# MainPage.net
KiCad netlist of a schematic drawn in Altium Designer
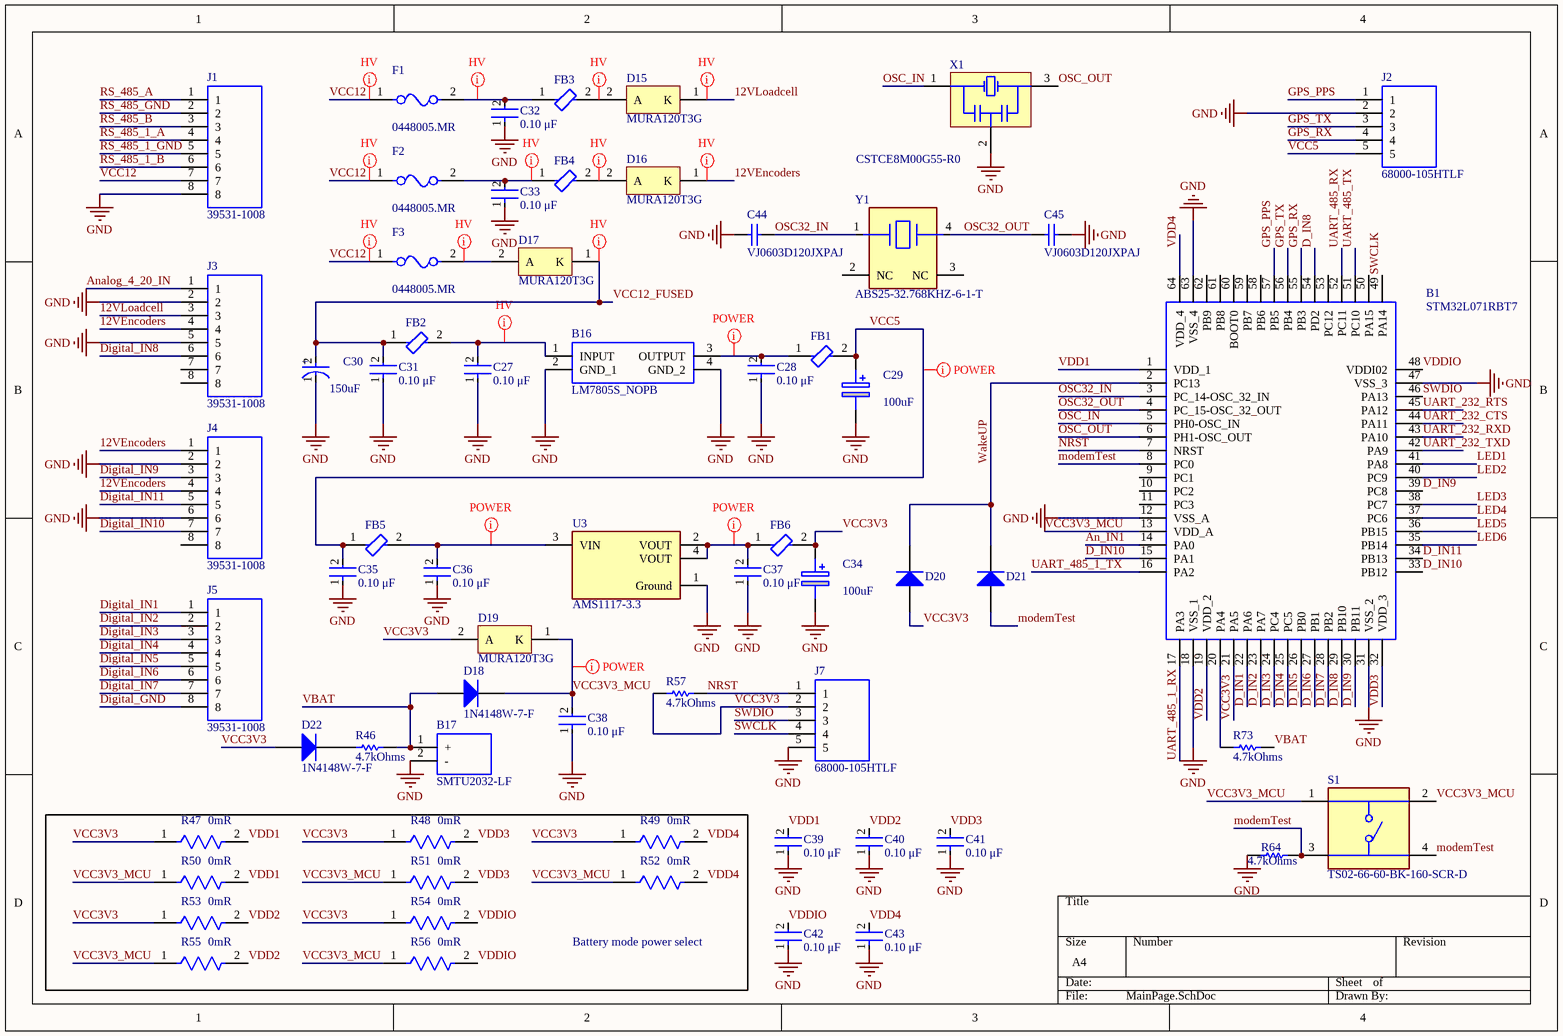
[diagram p0: MainPage.SchDoc]

(export (version "E")
  (design (tool "Eeschema 10.0.6"))
  (components
    (comp (ref "B1")
      (value "STM32L071RBT7")
      (footprint "QFP50P1200X1200X160-64N")
      (description "ARM Microcontrollers - MCU 16/32-BITS MICROS")
      (fields (field (name "MOUSER PART NUMBER") "511-STM32L071RBT7"))
      (libsource (lib "Schlib2") (part "STM32L071RBT7"))
    )
    (comp (ref "B16")
      (value "LM7805S_NOPB")
      (footprint "KTT0003B")
      (description "1.5-A, Wide VIN Fixed Voltage Regulators")
      (fields
        (field (name "MOUSER PART NUMBER") "595-LM7805S/NOPB")
        (field (name "MANUFACTURER_PART_NUMBER") "LM7805S/NOPB")
      )
      (libsource (lib "Schlib2") (part "LM7805S_NOPB"))
    )
    (comp (ref "B17")
      (value "SMTU2032-LF")
      (footprint "SMTU2032LF")
      (description "Coin Cell Battery Holders SFC MNT FOR CR2032")
      (fields (field (name "MOUSER PART NUMBER") "614-SMTU2032-LF"))
      (libsource (lib "Schlib2") (part "SMTU2032-LF"))
    )
    (comp (ref "C27")
      (value "0.10 μF")
      (footprint "FP-C0805C-DN-MFG")
      (description "C0805 0.10 μF X7R 30ppm/°C 10.00% 50 V")
      (fields
        (field (name "MANUFACTURER") "KEMET")
        (field (name "MANUFACTURER PART NUMBER") "C0805C104K5RAC7411")
      )
      (libsource (lib "Altium Content Vault") (part "b4654b650e69147ec39a6b967a45e02"))
    )
    (comp (ref "C28")
      (value "0.10 μF")
      (footprint "FP-C0805C-DN-MFG")
      (description "C0805 0.10 μF X7R 30ppm/°C 10.00% 50 V")
      (fields
        (field (name "MANUFACTURER") "KEMET")
        (field (name "MANUFACTURER PART NUMBER") "C0805C104K5RAC7411")
      )
      (libsource (lib "Altium Content Vault") (part "b4654b650e69147ec39a6b967a45e02"))
    )
    (comp (ref "C29")
      (value "T520B107M006ATE040")
      (footprint "T520B")
      (fields (field (name "MOUSER PART NUMBER") "80-T520B107M6ATE40") (field (name "CAPACITANCE") "100uF"))
      (libsource (lib "Schlib2") (part "T520B107M006ATE040"))
    )
    (comp (ref "C30")
      (value "TAJE157K020RNJ")
      (footprint "FP-TAJE-MFG")
      (description "150uF 20V  ±10% 300mΩ 2917  SMD Tantalum Capacitor")
      (fields (field (name "CAPACITANCE") "150uF") (field (name "TOLERANCE") "10%"))
      (libsource (lib "Altium Content Vault") (part "203bc49f2ac43e59fd269a8c329ed05"))
    )
    (comp (ref "C31")
      (value "0.10 μF")
      (footprint "FP-C0805C-DN-MFG")
      (description "C0805 0.10 μF X7R 30ppm/°C 10.00% 50 V")
      (fields
        (field (name "MANUFACTURER") "KEMET")
        (field (name "MANUFACTURER PART NUMBER") "C0805C104K5RAC7411")
      )
      (libsource (lib "Altium Content Vault") (part "b4654b650e69147ec39a6b967a45e02"))
    )
    (comp (ref "C32")
      (value "0.10 μF")
      (footprint "FP-C0805C-DN-MFG")
      (description "C0805 0.10 μF X7R 30ppm/°C 10.00% 50 V")
      (fields
        (field (name "MANUFACTURER") "KEMET")
        (field (name "MANUFACTURER PART NUMBER") "C0805C104K5RAC7411")
      )
      (libsource (lib "Altium Content Vault") (part "b4654b650e69147ec39a6b967a45e02"))
    )
    (comp (ref "C33")
      (value "0.10 μF")
      (footprint "FP-C0805C-DN-MFG")
      (description "C0805 0.10 μF X7R 30ppm/°C 10.00% 50 V")
      (fields
        (field (name "MANUFACTURER") "KEMET")
        (field (name "MANUFACTURER PART NUMBER") "C0805C104K5RAC7411")
      )
      (libsource (lib "Altium Content Vault") (part "b4654b650e69147ec39a6b967a45e02"))
    )
    (comp (ref "C34")
      (value "T520B107M006ATE040")
      (footprint "T520B")
      (fields (field (name "MOUSER PART NUMBER") "80-T520B107M6ATE40") (field (name "CAPACITANCE") "100uF"))
      (libsource (lib "Schlib2") (part "T520B107M006ATE040"))
    )
    (comp (ref "C35")
      (value "0.10 μF")
      (footprint "FP-C0805C-DN-MFG")
      (description "C0805 0.10 μF X7R 30ppm/°C 10.00% 50 V")
      (fields
        (field (name "MANUFACTURER") "KEMET")
        (field (name "MANUFACTURER PART NUMBER") "C0805C104K5RAC7411")
      )
      (libsource (lib "Altium Content Vault") (part "b4654b650e69147ec39a6b967a45e02"))
    )
    (comp (ref "C36")
      (value "0.10 μF")
      (footprint "FP-C0805C-DN-MFG")
      (description "C0805 0.10 μF X7R 30ppm/°C 10.00% 50 V")
      (fields
        (field (name "MANUFACTURER") "KEMET")
        (field (name "MANUFACTURER PART NUMBER") "C0805C104K5RAC7411")
      )
      (libsource (lib "Altium Content Vault") (part "b4654b650e69147ec39a6b967a45e02"))
    )
    (comp (ref "C37")
      (value "0.10 μF")
      (footprint "FP-C0805C-DN-MFG")
      (description "C0805 0.10 μF X7R 30ppm/°C 10.00% 50 V")
      (fields
        (field (name "MANUFACTURER") "KEMET")
        (field (name "MANUFACTURER PART NUMBER") "C0805C104K5RAC7411")
      )
      (libsource (lib "Altium Content Vault") (part "b4654b650e69147ec39a6b967a45e02"))
    )
    (comp (ref "C38")
      (value "0.10 μF")
      (footprint "FP-C0805C-DN-MFG")
      (description "C0805 0.10 μF X7R 30ppm/°C 10.00% 50 V")
      (fields
        (field (name "MANUFACTURER") "KEMET")
        (field (name "MANUFACTURER PART NUMBER") "C0805C104K5RAC7411")
      )
      (libsource (lib "Altium Content Vault") (part "b4654b650e69147ec39a6b967a45e02"))
    )
    (comp (ref "C39")
      (value "0.10 μF")
      (footprint "FP-C0805C-DN-MFG")
      (description "C0805 0.10 μF X7R 30ppm/°C 10.00% 50 V")
      (fields
        (field (name "MANUFACTURER") "KEMET")
        (field (name "MANUFACTURER PART NUMBER") "C0805C104K5RAC7411")
      )
      (libsource (lib "Altium Content Vault") (part "b4654b650e69147ec39a6b967a45e02"))
    )
    (comp (ref "C40")
      (value "0.10 μF")
      (footprint "FP-C0805C-DN-MFG")
      (description "C0805 0.10 μF X7R 30ppm/°C 10.00% 50 V")
      (fields
        (field (name "MANUFACTURER") "KEMET")
        (field (name "MANUFACTURER PART NUMBER") "C0805C104K5RAC7411")
      )
      (libsource (lib "Altium Content Vault") (part "b4654b650e69147ec39a6b967a45e02"))
    )
    (comp (ref "C41")
      (value "0.10 μF")
      (footprint "FP-C0805C-DN-MFG")
      (description "C0805 0.10 μF X7R 30ppm/°C 10.00% 50 V")
      (fields
        (field (name "MANUFACTURER") "KEMET")
        (field (name "MANUFACTURER PART NUMBER") "C0805C104K5RAC7411")
      )
      (libsource (lib "Altium Content Vault") (part "b4654b650e69147ec39a6b967a45e02"))
    )
    (comp (ref "C42")
      (value "0.10 μF")
      (footprint "FP-C0805C-DN-MFG")
      (description "C0805 0.10 μF X7R 30ppm/°C 10.00% 50 V")
      (fields
        (field (name "MANUFACTURER") "KEMET")
        (field (name "MANUFACTURER PART NUMBER") "C0805C104K5RAC7411")
      )
      (libsource (lib "Altium Content Vault") (part "b4654b650e69147ec39a6b967a45e02"))
    )
    (comp (ref "C43")
      (value "0.10 μF")
      (footprint "FP-C0805C-DN-MFG")
      (description "C0805 0.10 μF X7R 30ppm/°C 10.00% 50 V")
      (fields
        (field (name "MANUFACTURER") "KEMET")
        (field (name "MANUFACTURER PART NUMBER") "C0805C104K5RAC7411")
      )
      (libsource (lib "Altium Content Vault") (part "b4654b650e69147ec39a6b967a45e02"))
    )
    (comp (ref "C44")
      (value "VJ0603D120JXPAJ")
      (footprint "CAPC1608X92X38LL15T08")
      (fields (field (name "MANUFACTURER") "Vitramon"))
      (libsource (lib "Altium Content Vault") (part "CAP"))
    )
    (comp (ref "C45")
      (value "VJ0603D120JXPAJ")
      (footprint "CAPC1608X92X38LL15T08")
      (fields (field (name "MANUFACTURER") "Vitramon"))
      (libsource (lib "Altium Content Vault") (part "CAP"))
    )
    (comp (ref "D15")
      (value "MURA120T3G")
      (footprint "ONSC-SMA-2-403D-02_V")
      (description "Surface Mount Ultrafast Power Rectifier, 2-Pin SMA, Pb-Free, Tape and Reel")
      (fields (field (name "MANUFACTURER") "On Semiconductor"))
      (libsource (lib "Altium Content Vault") (part "ONSC-D-K1A2-2_A"))
    )
    (comp (ref "D16")
      (value "MURA120T3G")
      (footprint "ONSC-SMA-2-403D-02_V")
      (description "Surface Mount Ultrafast Power Rectifier, 2-Pin SMA, Pb-Free, Tape and Reel")
      (fields (field (name "MANUFACTURER") "On Semiconductor"))
      (libsource (lib "Altium Content Vault") (part "ONSC-D-K1A2-2_A"))
    )
    (comp (ref "D17")
      (value "MURA120T3G")
      (footprint "ONSC-SMA-2-403D-02_V")
      (description "Surface Mount Ultrafast Power Rectifier, 2-Pin SMA, Pb-Free, Tape and Reel")
      (fields (field (name "MANUFACTURER") "On Semiconductor"))
      (libsource (lib "Altium Content Vault") (part "ONSC-D-K1A2-2_A"))
    )
    (comp (ref "D18")
      (value "1N4148W-7-F")
      (footprint "DIOD-SOD123-2_V")
      (description "Fast Switching Diode, 100 V, 0.15 A, -65 to 150 degC, 2-Pin?SOD123, RoHS, Tape and Reel")
      (fields (field (name "MANUFACTURER") "DiodesIncorporated"))
      (libsource (lib "Altium Content Vault") (part "D-AK-2"))
    )
    (comp (ref "D19")
      (value "MURA120T3G")
      (footprint "ONSC-SMA-2-403D-02_V")
      (description "Surface Mount Ultrafast Power Rectifier, 2-Pin SMA, Pb-Free, Tape and Reel")
      (fields (field (name "MANUFACTURER") "On Semiconductor"))
      (libsource (lib "Altium Content Vault") (part "ONSC-D-K1A2-2_A"))
    )
    (comp (ref "D20")
      (value "1N4148W-7-F")
      (footprint "DIOD-SOD123-2_V")
      (description "Fast Switching Diode, 100 V, 0.15 A, -65 to 150 degC, 2-Pin?SOD123, RoHS, Tape and Reel")
      (fields (field (name "MANUFACTURER") "DiodesIncorporated"))
      (libsource (lib "Altium Content Vault") (part "D-AK-2"))
    )
    (comp (ref "D21")
      (value "1N4148W-7-F")
      (footprint "DIOD-SOD123-2_V")
      (description "Fast Switching Diode, 100 V, 0.15 A, -65 to 150 degC, 2-Pin?SOD123, RoHS, Tape and Reel")
      (fields (field (name "MANUFACTURER") "DiodesIncorporated"))
      (libsource (lib "Altium Content Vault") (part "D-AK-2"))
    )
    (comp (ref "D22")
      (value "1N4148W-7-F")
      (footprint "DIOD-SOD123-2_V")
      (description "Fast Switching Diode, 100 V, 0.15 A, -65 to 150 degC, 2-Pin?SOD123, RoHS, Tape and Reel")
      (fields (field (name "MANUFACTURER") "DiodesIncorporated"))
      (libsource (lib "Altium Content Vault") (part "D-AK-2"))
    )
    (comp (ref "F1")
      (value "0448005.MR")
      (footprint "FP-0448-MFG")
      (description "FUSE BRD MNT 5A 125VAC/VDC 2SMD")
      (fields
        (field (name "OCTOPART") "https://octopart.com/0448005.mr-littelfuse-672815")
        (field (name "MANUFACTURER") "Littelfuse")
      )
      (libsource (lib "Altium Content Vault") (part "5bcf9b9f640e542cf0359d10258e979"))
    )
    (comp (ref "F2")
      (value "0448005.MR")
      (footprint "FP-0448-MFG")
      (description "FUSE BRD MNT 5A 125VAC/VDC 2SMD")
      (fields
        (field (name "OCTOPART") "https://octopart.com/0448005.mr-littelfuse-672815")
        (field (name "MANUFACTURER") "Littelfuse")
      )
      (libsource (lib "Altium Content Vault") (part "5bcf9b9f640e542cf0359d10258e979"))
    )
    (comp (ref "F3")
      (value "0448005.MR")
      (footprint "FP-0448-MFG")
      (description "FUSE BRD MNT 5A 125VAC/VDC 2SMD")
      (fields
        (field (name "OCTOPART") "https://octopart.com/0448005.mr-littelfuse-672815")
        (field (name "MANUFACTURER") "Littelfuse")
      )
      (libsource (lib "Altium Content Vault") (part "5bcf9b9f640e542cf0359d10258e979"))
    )
    (comp (ref "FB1")
      (value "BLM41PG181SH1L")
      (footprint "FP-BLM41-0_2-a1_2-MFG")
      (description "Ferrite Bead, 1806, 180Ω @ 100MHz, 25%, 0.02Ω, 3.5A")
      (fields (field (name "TOLERANCE") "25%"))
      (libsource (lib "Altium Content Vault") (part "5f30dd21d616792df468990f7003faa"))
    )
    (comp (ref "FB2")
      (value "BLM41PG181SH1L")
      (footprint "FP-BLM41-0_2-a1_2-MFG")
      (description "Ferrite Bead, 1806, 180Ω @ 100MHz, 25%, 0.02Ω, 3.5A")
      (fields (field (name "TOLERANCE") "25%"))
      (libsource (lib "Altium Content Vault") (part "5f30dd21d616792df468990f7003faa"))
    )
    (comp (ref "FB3")
      (value "BLM41PG181SH1L")
      (footprint "FP-BLM41-0_2-a1_2-MFG")
      (description "Ferrite Bead, 1806, 180Ω @ 100MHz, 25%, 0.02Ω, 3.5A")
      (fields (field (name "TOLERANCE") "25%"))
      (libsource (lib "Altium Content Vault") (part "5f30dd21d616792df468990f7003faa"))
    )
    (comp (ref "FB4")
      (value "BLM41PG181SH1L")
      (footprint "FP-BLM41-0_2-a1_2-MFG")
      (description "Ferrite Bead, 1806, 180Ω @ 100MHz, 25%, 0.02Ω, 3.5A")
      (fields (field (name "TOLERANCE") "25%"))
      (libsource (lib "Altium Content Vault") (part "5f30dd21d616792df468990f7003faa"))
    )
    (comp (ref "FB5")
      (value "BLM41PG181SH1L")
      (footprint "FP-BLM41-0_2-a1_2-MFG")
      (description "Ferrite Bead, 1806, 180Ω @ 100MHz, 25%, 0.02Ω, 3.5A")
      (fields (field (name "TOLERANCE") "25%"))
      (libsource (lib "Altium Content Vault") (part "5f30dd21d616792df468990f7003faa"))
    )
    (comp (ref "FB6")
      (value "BLM41PG181SH1L")
      (footprint "FP-BLM41-0_2-a1_2-MFG")
      (description "Ferrite Bead, 1806, 180Ω @ 100MHz, 25%, 0.02Ω, 3.5A")
      (fields (field (name "TOLERANCE") "25%"))
      (libsource (lib "Altium Content Vault") (part "5f30dd21d616792df468990f7003faa"))
    )
    (comp (ref "J1")
      (value "39531-1008")
      (footprint "RHDR8W140P0X508_1X8_4264X830X1240P")
      (description "Pluggable Terminal Blocks 5.08MM EURO HEADER VERT BLK 8CKT")
      (fields (field (name "MOUSER PART NUMBER") "538-39531-1008"))
      (libsource (lib "Schlib2") (part "39531-1008"))
    )
    (comp (ref "J2")
      (value "68000-105HTLF")
      (footprint "HDRV5W67P0X254_1X5_1270X241X858P")
      (description "68000-105HTLF-B/S SR HDR 1*5")
      (fields (field (name "MOUSER PART NUMBER") "649-68000-105HTLF"))
      (libsource (lib "Schlib2") (part "68000-105HTLF"))
    )
    (comp (ref "J3")
      (value "39531-1008")
      (footprint "RHDR8W140P0X508_1X8_4264X830X1240P")
      (description "Pluggable Terminal Blocks 5.08MM EURO HEADER VERT BLK 8CKT")
      (fields (field (name "MOUSER PART NUMBER") "538-39531-1008"))
      (libsource (lib "Schlib2") (part "39531-1008"))
    )
    (comp (ref "J4")
      (value "39531-1008")
      (footprint "RHDR8W140P0X508_1X8_4264X830X1240P")
      (description "Pluggable Terminal Blocks 5.08MM EURO HEADER VERT BLK 8CKT")
      (fields (field (name "MOUSER PART NUMBER") "538-39531-1008"))
      (libsource (lib "Schlib2") (part "39531-1008"))
    )
    (comp (ref "J5")
      (value "39531-1008")
      (footprint "RHDR8W140P0X508_1X8_4264X830X1240P")
      (description "Pluggable Terminal Blocks 5.08MM EURO HEADER VERT BLK 8CKT")
      (fields (field (name "MOUSER PART NUMBER") "538-39531-1008"))
      (libsource (lib "Schlib2") (part "39531-1008"))
    )
    (comp (ref "J7")
      (value "68000-105HTLF")
      (footprint "HDRV5W67P0X254_1X5_1270X241X858P")
      (description "68000-105HTLF-B/S SR HDR 1*5")
      (fields (field (name "MOUSER PART NUMBER") "649-68000-105HTLF"))
      (libsource (lib "Schlib2") (part "68000-105HTLF"))
    )
    (comp (ref "R46")
      (value "RC0603FR-074K7L")
      (footprint "RESC1608X55X25LL10T15")
      (description "Chip Resistor, 4.7 KOhm, +/- 1%, 0.1 W, -55 to 155 degC, 0603 (1608 Metric), RoHS, Tape and Reel")
      (fields
        (field (name "MANUFACTURER") "Yageo")
        (field (name "RESISTANCE") "4.7kOhms")
        (field (name "TOLERANCE") "1%")
      )
      (libsource (lib "Altium Content Vault") (part "RES-2"))
    )
    (comp (ref "R47")
      (value "CRCW06030000Z0EAHP")
      (footprint "FP-CRCW0603-HPe3-MFG")
      (description "RES Thick Film, 0Ω, , 0.33W, , 0603")
      (fields (field (name "RESISTANCE") "0mR"))
      (libsource (lib "Altium Content Vault") (part "1029c3af85768c4190bb7ad29bc67b5"))
    )
    (comp (ref "R48")
      (value "CRCW06030000Z0EAHP")
      (footprint "FP-CRCW0603-HPe3-MFG")
      (description "RES Thick Film, 0Ω, , 0.33W, , 0603")
      (fields (field (name "RESISTANCE") "0mR"))
      (libsource (lib "Altium Content Vault") (part "1029c3af85768c4190bb7ad29bc67b5"))
    )
    (comp (ref "R49")
      (value "CRCW06030000Z0EAHP")
      (footprint "FP-CRCW0603-HPe3-MFG")
      (description "RES Thick Film, 0Ω, , 0.33W, , 0603")
      (fields (field (name "RESISTANCE") "0mR"))
      (libsource (lib "Altium Content Vault") (part "1029c3af85768c4190bb7ad29bc67b5"))
    )
    (comp (ref "R50")
      (value "CRCW06030000Z0EAHP")
      (footprint "FP-CRCW0603-HPe3-MFG")
      (description "RES Thick Film, 0Ω, , 0.33W, , 0603")
      (fields (field (name "RESISTANCE") "0mR"))
      (libsource (lib "Altium Content Vault") (part "1029c3af85768c4190bb7ad29bc67b5"))
    )
    (comp (ref "R51")
      (value "CRCW06030000Z0EAHP")
      (footprint "FP-CRCW0603-HPe3-MFG")
      (description "RES Thick Film, 0Ω, , 0.33W, , 0603")
      (fields (field (name "RESISTANCE") "0mR"))
      (libsource (lib "Altium Content Vault") (part "1029c3af85768c4190bb7ad29bc67b5"))
    )
    (comp (ref "R52")
      (value "CRCW06030000Z0EAHP")
      (footprint "FP-CRCW0603-HPe3-MFG")
      (description "RES Thick Film, 0Ω, , 0.33W, , 0603")
      (fields (field (name "RESISTANCE") "0mR"))
      (libsource (lib "Altium Content Vault") (part "1029c3af85768c4190bb7ad29bc67b5"))
    )
    (comp (ref "R53")
      (value "CRCW06030000Z0EAHP")
      (footprint "FP-CRCW0603-HPe3-MFG")
      (description "RES Thick Film, 0Ω, , 0.33W, , 0603")
      (fields (field (name "RESISTANCE") "0mR"))
      (libsource (lib "Altium Content Vault") (part "1029c3af85768c4190bb7ad29bc67b5"))
    )
    (comp (ref "R54")
      (value "CRCW06030000Z0EAHP")
      (footprint "FP-CRCW0603-HPe3-MFG")
      (description "RES Thick Film, 0Ω, , 0.33W, , 0603")
      (fields (field (name "RESISTANCE") "0mR"))
      (libsource (lib "Altium Content Vault") (part "1029c3af85768c4190bb7ad29bc67b5"))
    )
    (comp (ref "R55")
      (value "CRCW06030000Z0EAHP")
      (footprint "FP-CRCW0603-HPe3-MFG")
      (description "RES Thick Film, 0Ω, , 0.33W, , 0603")
      (fields (field (name "RESISTANCE") "0mR"))
      (libsource (lib "Altium Content Vault") (part "1029c3af85768c4190bb7ad29bc67b5"))
    )
    (comp (ref "R56")
      (value "CRCW06030000Z0EAHP")
      (footprint "FP-CRCW0603-HPe3-MFG")
      (description "RES Thick Film, 0Ω, , 0.33W, , 0603")
      (fields (field (name "RESISTANCE") "0mR"))
      (libsource (lib "Altium Content Vault") (part "1029c3af85768c4190bb7ad29bc67b5"))
    )
    (comp (ref "R57")
      (value "RC0603FR-074K7L")
      (footprint "RESC1608X55X25LL10T15")
      (description "Chip Resistor, 4.7 KOhm, +/- 1%, 0.1 W, -55 to 155 degC, 0603 (1608 Metric), RoHS, Tape and Reel")
      (fields
        (field (name "MANUFACTURER") "Yageo")
        (field (name "RESISTANCE") "4.7kOhms")
        (field (name "TOLERANCE") "1%")
      )
      (libsource (lib "Altium Content Vault") (part "RES-2"))
    )
    (comp (ref "R64")
      (value "RC0603FR-074K7L")
      (footprint "RESC1608X55X25LL10T15")
      (description "Chip Resistor, 4.7 KOhm, +/- 1%, 0.1 W, -55 to 155 degC, 0603 (1608 Metric), RoHS, Tape and Reel")
      (fields
        (field (name "MANUFACTURER") "Yageo")
        (field (name "RESISTANCE") "4.7kOhms")
        (field (name "TOLERANCE") "1%")
      )
      (libsource (lib "Altium Content Vault") (part "RES-2"))
    )
    (comp (ref "R73")
      (value "RC0603FR-074K7L")
      (footprint "RESC1608X55X25LL10T15")
      (description "Chip Resistor, 4.7 KOhm, +/- 1%, 0.1 W, -55 to 155 degC, 0603 (1608 Metric), RoHS, Tape and Reel")
      (fields
        (field (name "MANUFACTURER") "Yageo")
        (field (name "RESISTANCE") "4.7kOhms")
        (field (name "TOLERANCE") "1%")
      )
      (libsource (lib "Altium Content Vault") (part "RES-2"))
    )
    (comp (ref "S1")
      (value "TS02-66-60-BK-160-SCR-D")
      (footprint "SW_TS02-66-60-BK-160-SCR-D")
      (libsource (lib "Schlib2") (part "TS02-66-60-BK-160-SCR-D"))
    )
    (comp (ref "U3")
      (value "AMS1117-3.3")
      (footprint "FP-AMS1117-IPC_C")
      (description "LDO Voltage Regulators 1A, 3.3V")
      (fields
        (field (name "OCTOPART") "https://octopart.com/ams1117-3.3-advanced+monolithic+systems-25899300")
        (field (name "MANUFACTURER") "Advanced Monolithic Systems")
      )
      (libsource (lib "Altium Content Vault") (part "8bdbb5f8e77002000e30dd2845d0354"))
    )
    (comp (ref "X1")
      (value "CSTCE8M00G55-R0")
      (footprint "MURA-CSTCE_G_A-3_V")
      (description "Ceramic Resonator, 8 MHz, +/- 0.5%, -20 to 80 degC, 3-Pin SMD, RoHS, Tape and Reel")
      (fields (field (name "TOLERANCE") "0.5%") (field (name "MANUFACTURER") "Murata"))
      (libsource (lib "Altium Content Vault") (part "MURA-CSTCE_G_A-3"))
    )
    (comp (ref "Y1")
      (value "ABS25-32.768KHZ-6-1-T")
      (footprint "FP-ABS25-MFG")
      (description "CRYSTAL 32.7680KHZ 6PF SMD")
      (fields (field (name "TOLERANCE") "10ppm"))
      (libsource (lib "Altium Content Vault") (part "28be33c29b20f54059194caee89ade4"))
    )
  )
  (nets
    (net (code "1") (name "/12VEncoders") (class "Default")
      (node (ref "D16") (pin "1") (pinfunction "K_1") (pintype "passive"))
      (node (ref "J3") (pin "4") (pinfunction "4_4") (pintype "passive"))
      (node (ref "J4") (pin "1") (pinfunction "1_1") (pintype "passive"))
      (node (ref "J4") (pin "4") (pinfunction "4_4") (pintype "passive"))
    )
    (net (code "2") (name "/12VLoadcell") (class "Default")
      (node (ref "D15") (pin "1") (pinfunction "K_1") (pintype "passive"))
      (node (ref "J3") (pin "3") (pinfunction "3_3") (pintype "passive"))
    )
    (net (code "3") (name "/An_IN1") (class "Default")
      (node (ref "B1") (pin "14") (pinfunction "PA0_14") (pintype "passive"))
    )
    (net (code "4") (name "/Analog_4_20_IN") (class "Default")
      (node (ref "J3") (pin "1") (pinfunction "1_1") (pintype "passive"))
    )
    (net (code "5") (name "/D_IN1") (class "Default")
      (node (ref "B1") (pin "22") (pinfunction "PA6_22") (pintype "passive"))
    )
    (net (code "6") (name "/D_IN2") (class "Default")
      (node (ref "B1") (pin "23") (pinfunction "PA7_23") (pintype "passive"))
    )
    (net (code "7") (name "/D_IN3") (class "Default")
      (node (ref "B1") (pin "24") (pinfunction "PC4_24") (pintype "passive"))
    )
    (net (code "8") (name "/D_IN4") (class "Default")
      (node (ref "B1") (pin "25") (pinfunction "PC5_25") (pintype "passive"))
    )
    (net (code "9") (name "/D_IN5") (class "Default")
      (node (ref "B1") (pin "26") (pinfunction "PB0_26") (pintype "passive"))
    )
    (net (code "10") (name "/D_IN6") (class "Default")
      (node (ref "B1") (pin "27") (pinfunction "PB1_27") (pintype "passive"))
    )
    (net (code "11") (name "/D_IN7") (class "Default")
      (node (ref "B1") (pin "28") (pinfunction "PB2_28") (pintype "passive"))
    )
    (net (code "12") (name "/D_IN8") (class "Default")
      (node (ref "B1") (pin "29") (pinfunction "PB10_29") (pintype "passive"))
      (node (ref "B1") (pin "54") (pinfunction "PD2_54") (pintype "passive"))
    )
    (net (code "13") (name "/D_IN9") (class "Default")
      (node (ref "B1") (pin "30") (pinfunction "PB11_30") (pintype "passive"))
      (node (ref "B1") (pin "39") (pinfunction "PC8_39") (pintype "passive"))
    )
    (net (code "14") (name "/D_IN10") (class "Default")
      (node (ref "B1") (pin "15") (pinfunction "PA1_15") (pintype "passive"))
      (node (ref "B1") (pin "33") (pinfunction "PB12_33") (pintype "passive"))
    )
    (net (code "15") (name "/D_IN11") (class "Default")
      (node (ref "B1") (pin "34") (pinfunction "PB13_34") (pintype "passive"))
    )
    (net (code "16") (name "/Digital_GND") (class "Default")
      (node (ref "J5") (pin "8") (pinfunction "8_8") (pintype "passive"))
    )
    (net (code "17") (name "/Digital_IN1") (class "Default")
      (node (ref "J5") (pin "1") (pinfunction "1_1") (pintype "passive"))
    )
    (net (code "18") (name "/Digital_IN2") (class "Default")
      (node (ref "J5") (pin "2") (pinfunction "2_2") (pintype "passive"))
    )
    (net (code "19") (name "/Digital_IN3") (class "Default")
      (node (ref "J5") (pin "3") (pinfunction "3_3") (pintype "passive"))
    )
    (net (code "20") (name "/Digital_IN4") (class "Default")
      (node (ref "J5") (pin "4") (pinfunction "4_4") (pintype "passive"))
    )
    (net (code "21") (name "/Digital_IN5") (class "Default")
      (node (ref "J5") (pin "5") (pinfunction "5_5") (pintype "passive"))
    )
    (net (code "22") (name "/Digital_IN6") (class "Default")
      (node (ref "J5") (pin "6") (pinfunction "6_6") (pintype "passive"))
    )
    (net (code "23") (name "/Digital_IN7") (class "Default")
      (node (ref "J5") (pin "7") (pinfunction "7_7") (pintype "passive"))
    )
    (net (code "24") (name "/Digital_IN8") (class "Default")
      (node (ref "J3") (pin "6") (pinfunction "6_6") (pintype "passive"))
    )
    (net (code "25") (name "/Digital_IN9") (class "Default")
      (node (ref "J4") (pin "3") (pinfunction "3_3") (pintype "passive"))
    )
    (net (code "26") (name "/Digital_IN10") (class "Default")
      (node (ref "J4") (pin "7") (pinfunction "7_7") (pintype "passive"))
    )
    (net (code "27") (name "/Digital_IN11") (class "Default")
      (node (ref "J4") (pin "5") (pinfunction "5_5") (pintype "passive"))
    )
    (net (code "28") (name "/GPS_PPS") (class "Default")
      (node (ref "B1") (pin "57") (pinfunction "PB5_57") (pintype "passive"))
      (node (ref "J2") (pin "1") (pinfunction "1_1") (pintype "passive"))
    )
    (net (code "29") (name "/GPS_RX") (class "Default")
      (node (ref "B1") (pin "55") (pinfunction "PB3_55") (pintype "passive"))
      (node (ref "J2") (pin "4") (pinfunction "4_4") (pintype "passive"))
    )
    (net (code "30") (name "/GPS_TX") (class "Default")
      (node (ref "B1") (pin "56") (pinfunction "PB4_56") (pintype "passive"))
      (node (ref "J2") (pin "3") (pinfunction "3_3") (pintype "passive"))
    )
    (net (code "31") (name "/LED1") (class "Default")
      (node (ref "B1") (pin "41") (pinfunction "PA8_41") (pintype "passive"))
    )
    (net (code "32") (name "/LED2") (class "Default")
      (node (ref "B1") (pin "40") (pinfunction "PC9_40") (pintype "passive"))
    )
    (net (code "33") (name "/LED3") (class "Default")
      (node (ref "B1") (pin "38") (pinfunction "PC7_38") (pintype "passive"))
    )
    (net (code "34") (name "/LED4") (class "Default")
      (node (ref "B1") (pin "37") (pinfunction "PC6_37") (pintype "passive"))
    )
    (net (code "35") (name "/LED5") (class "Default")
      (node (ref "B1") (pin "36") (pinfunction "PB15_36") (pintype "passive"))
    )
    (net (code "36") (name "/LED6") (class "Default")
      (node (ref "B1") (pin "35") (pinfunction "PB14_35") (pintype "passive"))
    )
    (net (code "37") (name "/NRST") (class "Default")
      (node (ref "B1") (pin "7") (pinfunction "NRST_7") (pintype "passive"))
      (node (ref "J7") (pin "1") (pinfunction "1_1") (pintype "passive"))
      (node (ref "R57") (pin "1") (pinfunction "1_1") (pintype "passive"))
    )
    (net (code "38") (name "/OSC32_IN") (class "Default")
      (node (ref "B1") (pin "3") (pinfunction "PC_14-OSC_32_IN_3") (pintype "passive"))
      (node (ref "C44") (pin "2") (pinfunction "2_2") (pintype "passive"))
      (node (ref "Y1") (pin "1") (pinfunction "1_1") (pintype "passive"))
    )
    (net (code "39") (name "/OSC32_OUT") (class "Default")
      (node (ref "B1") (pin "4") (pinfunction "PC_15-OSC_32_OUT_4") (pintype "passive"))
      (node (ref "C45") (pin "1") (pinfunction "1_1") (pintype "passive"))
      (node (ref "Y1") (pin "4") (pinfunction "4_4") (pintype "passive"))
    )
    (net (code "40") (name "/OSC_IN") (class "Default")
      (node (ref "B1") (pin "5") (pinfunction "PH0-OSC_IN_5") (pintype "passive"))
      (node (ref "X1") (pin "1") (pinfunction "X1_1") (pintype "passive"))
    )
    (net (code "41") (name "/OSC_OUT") (class "Default")
      (node (ref "B1") (pin "6") (pinfunction "PH1-OSC_OUT_6") (pintype "passive"))
      (node (ref "X1") (pin "3") (pinfunction "X2_3") (pintype "passive"))
    )
    (net (code "42") (name "/RS_485_1_A") (class "Default")
      (node (ref "J1") (pin "4") (pinfunction "4_4") (pintype "passive"))
    )
    (net (code "43") (name "/RS_485_1_B") (class "Default")
      (node (ref "J1") (pin "6") (pinfunction "6_6") (pintype "passive"))
    )
    (net (code "44") (name "/RS_485_1_GND") (class "Default")
      (node (ref "J1") (pin "5") (pinfunction "5_5") (pintype "passive"))
    )
    (net (code "45") (name "/RS_485_A") (class "Default")
      (node (ref "J1") (pin "1") (pinfunction "1_1") (pintype "passive"))
    )
    (net (code "46") (name "/RS_485_B") (class "Default")
      (node (ref "J1") (pin "3") (pinfunction "3_3") (pintype "passive"))
    )
    (net (code "47") (name "/RS_485_GND") (class "Default")
      (node (ref "J1") (pin "2") (pinfunction "2_2") (pintype "passive"))
    )
    (net (code "48") (name "/SWCLK") (class "Default")
      (node (ref "B1") (pin "49") (pinfunction "PA14_49") (pintype "passive"))
      (node (ref "J7") (pin "4") (pinfunction "4_4") (pintype "passive"))
    )
    (net (code "49") (name "/SWDIO") (class "Default")
      (node (ref "B1") (pin "46") (pinfunction "PA13_46") (pintype "passive"))
      (node (ref "J7") (pin "3") (pinfunction "3_3") (pintype "passive"))
    )
    (net (code "50") (name "/UART_232_CTS") (class "Default")
      (node (ref "B1") (pin "44") (pinfunction "PA11_44") (pintype "passive"))
    )
    (net (code "51") (name "/UART_232_RTS") (class "Default")
      (node (ref "B1") (pin "45") (pinfunction "PA12_45") (pintype "passive"))
    )
    (net (code "52") (name "/UART_232_RXD") (class "Default")
      (node (ref "B1") (pin "43") (pinfunction "PA10_43") (pintype "passive"))
    )
    (net (code "53") (name "/UART_232_TXD") (class "Default")
      (node (ref "B1") (pin "42") (pinfunction "PA9_42") (pintype "passive"))
    )
    (net (code "54") (name "/UART_485_1_RX") (class "Default")
      (node (ref "B1") (pin "17") (pinfunction "PA3_17") (pintype "passive"))
    )
    (net (code "55") (name "/UART_485_1_TX") (class "Default")
      (node (ref "B1") (pin "16") (pinfunction "PA2_16") (pintype "passive"))
    )
    (net (code "56") (name "/UART_485_RX") (class "Default")
      (node (ref "B1") (pin "52") (pinfunction "PC11_52") (pintype "passive"))
    )
    (net (code "57") (name "/UART_485_TX") (class "Default")
      (node (ref "B1") (pin "51") (pinfunction "PC10_51") (pintype "passive"))
    )
    (net (code "58") (name "/VBAT") (class "Default")
      (node (ref "B17") (pin "1") (pinfunction "+_1") (pintype "passive"))
      (node (ref "D18") (pin "1") (pinfunction "A_1") (pintype "passive"))
      (node (ref "R46") (pin "1") (pinfunction "1_1") (pintype "passive"))
      (node (ref "R73") (pin "1") (pinfunction "1_1") (pintype "passive"))
    )
    (net (code "59") (name "/VCC3V3") (class "Default")
      (node (ref "B1") (pin "21") (pinfunction "PA5_21") (pintype "passive"))
      (node (ref "C34") (pin "1") (pinfunction "+_1") (pintype "passive"))
      (node (ref "D19") (pin "2") (pinfunction "A_2") (pintype "passive"))
      (node (ref "D20") (pin "1") (pinfunction "A_1") (pintype "passive"))
      (node (ref "D22") (pin "1") (pinfunction "A_1") (pintype "passive"))
      (node (ref "FB6") (pin "2") (pinfunction "2_2") (pintype "passive"))
      (node (ref "J7") (pin "2") (pinfunction "2_2") (pintype "passive"))
      (node (ref "R47") (pin "1") (pinfunction "1_1") (pintype "passive"))
      (node (ref "R48") (pin "1") (pinfunction "1_1") (pintype "passive"))
      (node (ref "R49") (pin "1") (pinfunction "1_1") (pintype "passive"))
      (node (ref "R53") (pin "1") (pinfunction "1_1") (pintype "passive"))
      (node (ref "R54") (pin "1") (pinfunction "1_1") (pintype "passive"))
      (node (ref "R57") (pin "2") (pinfunction "2_2") (pintype "passive"))
    )
    (net (code "60") (name "/VCC3V3_MCU") (class "Default")
      (node (ref "B1") (pin "13") (pinfunction "VDD_A_13") (pintype "passive"))
      (node (ref "C38") (pin "2") (pinfunction "2_2") (pintype "passive"))
      (node (ref "D18") (pin "2") (pinfunction "K_2") (pintype "passive"))
      (node (ref "D19") (pin "1") (pinfunction "K_1") (pintype "passive"))
      (node (ref "R50") (pin "1") (pinfunction "1_1") (pintype "passive"))
      (node (ref "R51") (pin "1") (pinfunction "1_1") (pintype "passive"))
      (node (ref "R52") (pin "1") (pinfunction "1_1") (pintype "passive"))
      (node (ref "R55") (pin "1") (pinfunction "1_1") (pintype "passive"))
      (node (ref "R56") (pin "1") (pinfunction "1_1") (pintype "passive"))
      (node (ref "S1") (pin "1") (pinfunction "1_1") (pintype "passive"))
      (node (ref "S1") (pin "2") (pinfunction "2_2") (pintype "passive"))
    )
    (net (code "61") (name "/VCC5") (class "Default")
      (node (ref "C29") (pin "1") (pinfunction "+_1") (pintype "passive"))
      (node (ref "C35") (pin "2") (pinfunction "2_2") (pintype "passive"))
      (node (ref "FB1") (pin "2") (pinfunction "2_2") (pintype "passive"))
      (node (ref "FB5") (pin "1") (pinfunction "1_1") (pintype "passive"))
      (node (ref "J2") (pin "5") (pinfunction "5_5") (pintype "passive"))
    )
    (net (code "62") (name "/VCC12") (class "Default")
      (node (ref "F1") (pin "1") (pinfunction "1_1") (pintype "passive"))
      (node (ref "F2") (pin "1") (pinfunction "1_1") (pintype "passive"))
      (node (ref "F3") (pin "1") (pinfunction "1_1") (pintype "passive"))
      (node (ref "J1") (pin "7") (pinfunction "7_7") (pintype "passive"))
    )
    (net (code "63") (name "/VCC12_FUSED") (class "Default")
      (node (ref "C30") (pin "2") (pinfunction "A_2") (pintype "passive"))
      (node (ref "C31") (pin "2") (pinfunction "2_2") (pintype "passive"))
      (node (ref "D17") (pin "1") (pinfunction "K_1") (pintype "passive"))
      (node (ref "FB2") (pin "1") (pinfunction "1_1") (pintype "passive"))
    )
    (net (code "64") (name "/VDD1") (class "Default")
      (node (ref "B1") (pin "1") (pinfunction "VDD_1_1") (pintype "passive"))
      (node (ref "C39") (pin "2") (pinfunction "2_2") (pintype "passive"))
      (node (ref "R47") (pin "2") (pinfunction "2_2") (pintype "passive"))
      (node (ref "R50") (pin "2") (pinfunction "2_2") (pintype "passive"))
    )
    (net (code "65") (name "/VDD2") (class "Default")
      (node (ref "B1") (pin "19") (pinfunction "VDD_2_19") (pintype "passive"))
      (node (ref "C40") (pin "2") (pinfunction "2_2") (pintype "passive"))
      (node (ref "R53") (pin "2") (pinfunction "2_2") (pintype "passive"))
      (node (ref "R55") (pin "2") (pinfunction "2_2") (pintype "passive"))
    )
    (net (code "66") (name "/VDD3") (class "Default")
      (node (ref "B1") (pin "32") (pinfunction "VDD_3_32") (pintype "passive"))
      (node (ref "C41") (pin "2") (pinfunction "2_2") (pintype "passive"))
      (node (ref "R48") (pin "2") (pinfunction "2_2") (pintype "passive"))
      (node (ref "R51") (pin "2") (pinfunction "2_2") (pintype "passive"))
    )
    (net (code "67") (name "/VDD4") (class "Default")
      (node (ref "B1") (pin "64") (pinfunction "VDD_4_64") (pintype "passive"))
      (node (ref "C43") (pin "2") (pinfunction "2_2") (pintype "passive"))
      (node (ref "R49") (pin "2") (pinfunction "2_2") (pintype "passive"))
      (node (ref "R52") (pin "2") (pinfunction "2_2") (pintype "passive"))
    )
    (net (code "68") (name "/VDDIO") (class "Default")
      (node (ref "B1") (pin "48") (pinfunction "VDDI02_48") (pintype "passive"))
      (node (ref "C42") (pin "2") (pinfunction "2_2") (pintype "passive"))
      (node (ref "R54") (pin "2") (pinfunction "2_2") (pintype "passive"))
      (node (ref "R56") (pin "2") (pinfunction "2_2") (pintype "passive"))
    )
    (net (code "69") (name "/WakeUP") (class "Default")
      (node (ref "B1") (pin "2") (pinfunction "PC13_2") (pintype "passive"))
      (node (ref "D20") (pin "2") (pinfunction "K_2") (pintype "passive"))
      (node (ref "D21") (pin "2") (pinfunction "K_2") (pintype "passive"))
    )
    (net (code "70") (name "/modemTest") (class "Default")
      (node (ref "B1") (pin "8") (pinfunction "PC0_8") (pintype "passive"))
      (node (ref "D21") (pin "1") (pinfunction "A_1") (pintype "passive"))
      (node (ref "R64") (pin "1") (pinfunction "1_1") (pintype "passive"))
      (node (ref "S1") (pin "3") (pinfunction "3_3") (pintype "passive"))
      (node (ref "S1") (pin "4") (pinfunction "4_4") (pintype "passive"))
    )
    (net (code "71") (name "GND") (class "Default")
      (node (ref "B1") (pin "12") (pinfunction "VSS_A_12") (pintype "passive"))
      (node (ref "B1") (pin "18") (pinfunction "VSS_1_18") (pintype "passive"))
      (node (ref "B1") (pin "31") (pinfunction "VSS_2_31") (pintype "passive"))
      (node (ref "B1") (pin "47") (pinfunction "VSS_3_47") (pintype "passive"))
      (node (ref "B1") (pin "63") (pinfunction "VSS_4_63") (pintype "passive"))
      (node (ref "B16") (pin "2") (pinfunction "GND_1_2") (pintype "passive"))
      (node (ref "B16") (pin "4") (pinfunction "GND_2_4") (pintype "passive"))
      (node (ref "B17") (pin "2") (pinfunction "-_2") (pintype "passive"))
      (node (ref "C27") (pin "1") (pinfunction "1_1") (pintype "passive"))
      (node (ref "C28") (pin "1") (pinfunction "1_1") (pintype "passive"))
      (node (ref "C29") (pin "2") (pinfunction "-_2") (pintype "passive"))
      (node (ref "C30") (pin "1") (pinfunction "C_1") (pintype "passive"))
      (node (ref "C31") (pin "1") (pinfunction "1_1") (pintype "passive"))
      (node (ref "C32") (pin "1") (pinfunction "1_1") (pintype "passive"))
      (node (ref "C33") (pin "1") (pinfunction "1_1") (pintype "passive"))
      (node (ref "C34") (pin "2") (pinfunction "-_2") (pintype "passive"))
      (node (ref "C35") (pin "1") (pinfunction "1_1") (pintype "passive"))
      (node (ref "C36") (pin "1") (pinfunction "1_1") (pintype "passive"))
      (node (ref "C37") (pin "1") (pinfunction "1_1") (pintype "passive"))
      (node (ref "C38") (pin "1") (pinfunction "1_1") (pintype "passive"))
      (node (ref "C39") (pin "1") (pinfunction "1_1") (pintype "passive"))
      (node (ref "C40") (pin "1") (pinfunction "1_1") (pintype "passive"))
      (node (ref "C41") (pin "1") (pinfunction "1_1") (pintype "passive"))
      (node (ref "C42") (pin "1") (pinfunction "1_1") (pintype "passive"))
      (node (ref "C43") (pin "1") (pinfunction "1_1") (pintype "passive"))
      (node (ref "C44") (pin "1") (pinfunction "1_1") (pintype "passive"))
      (node (ref "C45") (pin "2") (pinfunction "2_2") (pintype "passive"))
      (node (ref "J1") (pin "8") (pinfunction "8_8") (pintype "passive"))
      (node (ref "J2") (pin "2") (pinfunction "2_2") (pintype "passive"))
      (node (ref "J3") (pin "2") (pinfunction "2_2") (pintype "passive"))
      (node (ref "J3") (pin "5") (pinfunction "5_5") (pintype "passive"))
      (node (ref "J4") (pin "2") (pinfunction "2_2") (pintype "passive"))
      (node (ref "J4") (pin "6") (pinfunction "6_6") (pintype "passive"))
      (node (ref "J7") (pin "5") (pinfunction "5_5") (pintype "passive"))
      (node (ref "R64") (pin "2") (pinfunction "2_2") (pintype "passive"))
      (node (ref "U3") (pin "1") (pinfunction "Ground_1") (pintype "power_in"))
      (node (ref "X1") (pin "2") (pinfunction "GND_2") (pintype "power_in"))
    )
    (net (code "72") (name "Net-(B1-PA4)") (class "Default")
      (node (ref "B1") (pin "20") (pinfunction "PA4_20") (pintype "passive"))
      (node (ref "R73") (pin "2") (pinfunction "2_2") (pintype "passive"))
    )
    (net (code "73") (name "Net-(B16-INPUT)") (class "Default")
      (node (ref "B16") (pin "1") (pinfunction "INPUT_1") (pintype "passive"))
      (node (ref "C27") (pin "2") (pinfunction "2_2") (pintype "passive"))
      (node (ref "FB2") (pin "2") (pinfunction "2_2") (pintype "passive"))
    )
    (net (code "74") (name "Net-(B16-OUTPUT)") (class "Default")
      (node (ref "B16") (pin "3") (pinfunction "OUTPUT_3") (pintype "passive"))
      (node (ref "C28") (pin "2") (pinfunction "2_2") (pintype "passive"))
      (node (ref "FB1") (pin "1") (pinfunction "1_1") (pintype "passive"))
    )
    (net (code "75") (name "Net-(C32-Pad2)") (class "Default")
      (node (ref "C32") (pin "2") (pinfunction "2_2") (pintype "passive"))
      (node (ref "F1") (pin "2") (pinfunction "2_2") (pintype "passive"))
      (node (ref "FB3") (pin "1") (pinfunction "1_1") (pintype "passive"))
    )
    (net (code "76") (name "Net-(C33-Pad2)") (class "Default")
      (node (ref "C33") (pin "2") (pinfunction "2_2") (pintype "passive"))
      (node (ref "F2") (pin "2") (pinfunction "2_2") (pintype "passive"))
      (node (ref "FB4") (pin "1") (pinfunction "1_1") (pintype "passive"))
    )
    (net (code "77") (name "Net-(C37-Pad2)") (class "Default")
      (node (ref "C37") (pin "2") (pinfunction "2_2") (pintype "passive"))
      (node (ref "FB6") (pin "1") (pinfunction "1_1") (pintype "passive"))
      (node (ref "U3") (pin "2") (pinfunction "VOUT_2") (pintype "passive"))
      (node (ref "U3") (pin "4") (pinfunction "VOUT_4") (pintype "passive"))
    )
    (net (code "78") (name "Net-(D15-A)") (class "Default")
      (node (ref "D15") (pin "2") (pinfunction "A_2") (pintype "passive"))
      (node (ref "FB3") (pin "2") (pinfunction "2_2") (pintype "passive"))
    )
    (net (code "79") (name "Net-(D16-A)") (class "Default")
      (node (ref "D16") (pin "2") (pinfunction "A_2") (pintype "passive"))
      (node (ref "FB4") (pin "2") (pinfunction "2_2") (pintype "passive"))
    )
    (net (code "80") (name "Net-(D17-A)") (class "Default")
      (node (ref "D17") (pin "2") (pinfunction "A_2") (pintype "passive"))
      (node (ref "F3") (pin "2") (pinfunction "2_2") (pintype "passive"))
    )
    (net (code "81") (name "Net-(D22-K)") (class "Default")
      (node (ref "D22") (pin "2") (pinfunction "K_2") (pintype "passive"))
      (node (ref "R46") (pin "2") (pinfunction "2_2") (pintype "passive"))
    )
    (net (code "82") (name "Net-(U3-VIN)") (class "Default")
      (node (ref "C36") (pin "2") (pinfunction "2_2") (pintype "passive"))
      (node (ref "FB5") (pin "2") (pinfunction "2_2") (pintype "passive"))
      (node (ref "U3") (pin "3") (pinfunction "VIN_3") (pintype "power_in"))
    )
    (net (code "83") (name "unconnected-(B1-BOOT0-Pad60)") (class "Default")
      (node (ref "B1") (pin "60") (pinfunction "BOOT0_60") (pintype "passive"))
    )
    (net (code "84") (name "unconnected-(B1-PA15-Pad50)") (class "Default")
      (node (ref "B1") (pin "50") (pinfunction "PA15_50") (pintype "passive"))
    )
    (net (code "85") (name "unconnected-(B1-PB6-Pad58)") (class "Default")
      (node (ref "B1") (pin "58") (pinfunction "PB6_58") (pintype "passive"))
    )
    (net (code "86") (name "unconnected-(B1-PB7-Pad59)") (class "Default")
      (node (ref "B1") (pin "59") (pinfunction "PB7_59") (pintype "passive"))
    )
    (net (code "87") (name "unconnected-(B1-PB8-Pad61)") (class "Default")
      (node (ref "B1") (pin "61") (pinfunction "PB8_61") (pintype "passive"))
    )
    (net (code "88") (name "unconnected-(B1-PB9-Pad62)") (class "Default")
      (node (ref "B1") (pin "62") (pinfunction "PB9_62") (pintype "passive"))
    )
    (net (code "89") (name "unconnected-(B1-PC1-Pad9)") (class "Default")
      (node (ref "B1") (pin "9") (pinfunction "PC1_9") (pintype "passive"))
    )
    (net (code "90") (name "unconnected-(B1-PC2-Pad10)") (class "Default")
      (node (ref "B1") (pin "10") (pinfunction "PC2_10") (pintype "passive"))
    )
    (net (code "91") (name "unconnected-(B1-PC3-Pad11)") (class "Default")
      (node (ref "B1") (pin "11") (pinfunction "PC3_11") (pintype "passive"))
    )
    (net (code "92") (name "unconnected-(B1-PC12-Pad53)") (class "Default")
      (node (ref "B1") (pin "53") (pinfunction "PC12_53") (pintype "passive"))
    )
    (net (code "93") (name "unconnected-(J3-Pad7)") (class "Default")
      (node (ref "J3") (pin "7") (pinfunction "7_7") (pintype "passive"))
    )
    (net (code "94") (name "unconnected-(J3-Pad8)") (class "Default")
      (node (ref "J3") (pin "8") (pinfunction "8_8") (pintype "passive"))
    )
    (net (code "95") (name "unconnected-(J4-Pad8)") (class "Default")
      (node (ref "J4") (pin "8") (pinfunction "8_8") (pintype "passive"))
    )
    (net (code "96") (name "unconnected-(Y1-NC-Pad2)") (class "Default")
      (node (ref "Y1") (pin "2") (pinfunction "NC_2") (pintype "passive"))
    )
    (net (code "97") (name "unconnected-(Y1-NC-Pad3)") (class "Default")
      (node (ref "Y1") (pin "3") (pinfunction "NC_3") (pintype "passive"))
    )
  )
)
